# SUBBOARD-boost_filter_3p_LCL.net
KiCad netlist of a schematic drawn in Altium Designer
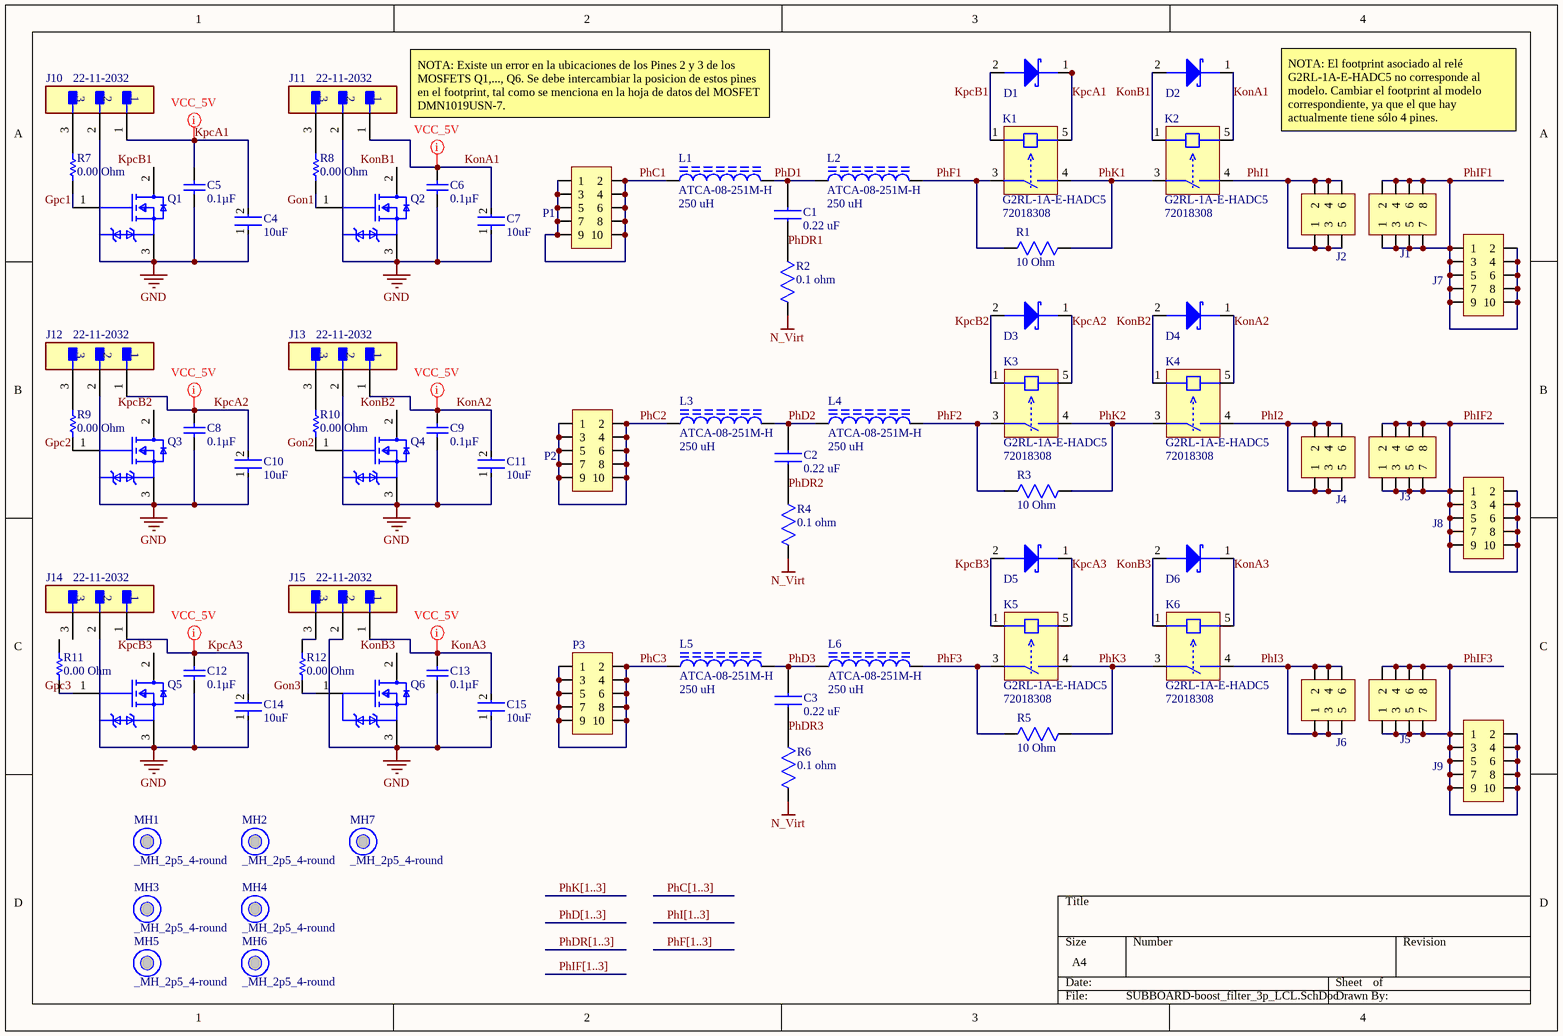
[diagram p0: SUBBOARD-boost_filter_3p_LCL.SchDoc]

(export (version "E")
  (design (tool "Eeschema 10.0.6"))
  (components
    (comp (ref "C1")
      (value "B32652A6224K")
      (footprint "B32652XXXXX")
      (description "Film Capacitors 0.22uF 630volts 5%")
      (fields
        (field (name "CAPACITANCE") "0.22 uF")
        (field (name "COPYRIGHT") "Copyright (C) 2018 Accelerated Designs. All rights reserved")
      )
      (libsource (lib "Altium_Library_POWERLAB") (part "B32652A6224K"))
    )
    (comp (ref "C2")
      (value "B32652A6224K")
      (footprint "B32652XXXXX")
      (description "Film Capacitors 0.22uF 630volts 5%")
      (fields
        (field (name "CAPACITANCE") "0.22 uF")
        (field (name "COPYRIGHT") "Copyright (C) 2018 Accelerated Designs. All rights reserved")
      )
      (libsource (lib "Altium_Library_POWERLAB") (part "B32652A6224K"))
    )
    (comp (ref "C3")
      (value "B32652A6224K")
      (footprint "B32652XXXXX")
      (description "Film Capacitors 0.22uF 630volts 5%")
      (fields
        (field (name "CAPACITANCE") "0.22 uF")
        (field (name "COPYRIGHT") "Copyright (C) 2018 Accelerated Designs. All rights reserved")
      )
      (libsource (lib "Altium_Library_POWERLAB") (part "B32652A6224K"))
    )
    (comp (ref "C4")
      (value "10uF")
      (footprint "FP-GRT31-0_2-MFG")
      (description "CAP CER 10UF 50V X5R 1206")
      (fields
        (field (name "TOLERANCE") "10%")
        (field (name "OCTOPART") "https://octopart.com/grt31cr61h106ke01l-murata-62921736")
      )
      (libsource (lib "Altium Content Vault") (part "11868f565c42a9108669ba33697ecf6"))
    )
    (comp (ref "C5")
      (value "CL10B104KB8NNNC")
      (footprint "SAMS-C0603-2_L")
      (description "Multi-layer Ceramic Capacitor, -55 to 125 degC, 2-Pin SMD (0603), RoHS, Tape and Reel")
      (fields (field (name "CAPACITANCE") "0.1µF") (field (name "MANUFACTURER") "Samsung Electro-Mechanics"))
      (libsource (lib "Altium Content Vault") (part "CAP-NP-2"))
    )
    (comp (ref "C6")
      (value "CL10B104KB8NNNC")
      (footprint "SAMS-C0603-2_L")
      (description "Multi-layer Ceramic Capacitor, -55 to 125 degC, 2-Pin SMD (0603), RoHS, Tape and Reel")
      (fields (field (name "CAPACITANCE") "0.1µF") (field (name "MANUFACTURER") "Samsung Electro-Mechanics"))
      (libsource (lib "Altium Content Vault") (part "CAP-NP-2"))
    )
    (comp (ref "C7")
      (value "10uF")
      (footprint "FP-GRT31-0_2-MFG")
      (description "CAP CER 10UF 50V X5R 1206")
      (fields
        (field (name "TOLERANCE") "10%")
        (field (name "OCTOPART") "https://octopart.com/grt31cr61h106ke01l-murata-62921736")
      )
      (libsource (lib "Altium Content Vault") (part "11868f565c42a9108669ba33697ecf6"))
    )
    (comp (ref "C8")
      (value "CL10B104KB8NNNC")
      (footprint "SAMS-C0603-2_L")
      (description "Multi-layer Ceramic Capacitor, -55 to 125 degC, 2-Pin SMD (0603), RoHS, Tape and Reel")
      (fields (field (name "CAPACITANCE") "0.1µF") (field (name "MANUFACTURER") "Samsung Electro-Mechanics"))
      (libsource (lib "Altium Content Vault") (part "CAP-NP-2"))
    )
    (comp (ref "C9")
      (value "CL10B104KB8NNNC")
      (footprint "SAMS-C0603-2_L")
      (description "Multi-layer Ceramic Capacitor, -55 to 125 degC, 2-Pin SMD (0603), RoHS, Tape and Reel")
      (fields (field (name "CAPACITANCE") "0.1µF") (field (name "MANUFACTURER") "Samsung Electro-Mechanics"))
      (libsource (lib "Altium Content Vault") (part "CAP-NP-2"))
    )
    (comp (ref "C10")
      (value "10uF")
      (footprint "FP-GRT31-0_2-MFG")
      (description "CAP CER 10UF 50V X5R 1206")
      (fields
        (field (name "TOLERANCE") "10%")
        (field (name "OCTOPART") "https://octopart.com/grt31cr61h106ke01l-murata-62921736")
      )
      (libsource (lib "Altium Content Vault") (part "11868f565c42a9108669ba33697ecf6"))
    )
    (comp (ref "C11")
      (value "10uF")
      (footprint "FP-GRT31-0_2-MFG")
      (description "CAP CER 10UF 50V X5R 1206")
      (fields
        (field (name "TOLERANCE") "10%")
        (field (name "OCTOPART") "https://octopart.com/grt31cr61h106ke01l-murata-62921736")
      )
      (libsource (lib "Altium Content Vault") (part "11868f565c42a9108669ba33697ecf6"))
    )
    (comp (ref "C12")
      (value "CL10B104KB8NNNC")
      (footprint "SAMS-C0603-2_L")
      (description "Multi-layer Ceramic Capacitor, -55 to 125 degC, 2-Pin SMD (0603), RoHS, Tape and Reel")
      (fields (field (name "CAPACITANCE") "0.1µF") (field (name "MANUFACTURER") "Samsung Electro-Mechanics"))
      (libsource (lib "Altium Content Vault") (part "CAP-NP-2"))
    )
    (comp (ref "C13")
      (value "CL10B104KB8NNNC")
      (footprint "SAMS-C0603-2_L")
      (description "Multi-layer Ceramic Capacitor, -55 to 125 degC, 2-Pin SMD (0603), RoHS, Tape and Reel")
      (fields (field (name "CAPACITANCE") "0.1µF") (field (name "MANUFACTURER") "Samsung Electro-Mechanics"))
      (libsource (lib "Altium Content Vault") (part "CAP-NP-2"))
    )
    (comp (ref "C14")
      (value "10uF")
      (footprint "FP-GRT31-0_2-MFG")
      (description "CAP CER 10UF 50V X5R 1206")
      (fields
        (field (name "TOLERANCE") "10%")
        (field (name "OCTOPART") "https://octopart.com/grt31cr61h106ke01l-murata-62921736")
      )
      (libsource (lib "Altium Content Vault") (part "11868f565c42a9108669ba33697ecf6"))
    )
    (comp (ref "C15")
      (value "10uF")
      (footprint "FP-GRT31-0_2-MFG")
      (description "CAP CER 10UF 50V X5R 1206")
      (fields
        (field (name "TOLERANCE") "10%")
        (field (name "OCTOPART") "https://octopart.com/grt31cr61h106ke01l-murata-62921736")
      )
      (libsource (lib "Altium Content Vault") (part "11868f565c42a9108669ba33697ecf6"))
    )
    (comp (ref "D1")
      (value "BYG23T-M3/TR")
      (footprint "BYG23T-M3/TR")
      (description "DIODE AVALANCHE 1300V 1A DO214AC")
      (fields (field (name "MANUFACTURER") "Vishay Semiconductors"))
      (libsource (lib "Altium_Library_POWERLAB") (part "BYG23T-M3/TR"))
    )
    (comp (ref "D2")
      (value "BYG23T-M3/TR")
      (footprint "BYG23T-M3/TR")
      (description "DIODE AVALANCHE 1300V 1A DO214AC")
      (fields (field (name "MANUFACTURER") "Vishay Semiconductors"))
      (libsource (lib "Altium_Library_POWERLAB") (part "BYG23T-M3/TR"))
    )
    (comp (ref "D3")
      (value "BYG23T-M3/TR")
      (footprint "BYG23T-M3/TR")
      (description "DIODE AVALANCHE 1300V 1A DO214AC")
      (fields (field (name "MANUFACTURER") "Vishay Semiconductors"))
      (libsource (lib "Altium_Library_POWERLAB") (part "BYG23T-M3/TR"))
    )
    (comp (ref "D4")
      (value "BYG23T-M3/TR")
      (footprint "BYG23T-M3/TR")
      (description "DIODE AVALANCHE 1300V 1A DO214AC")
      (fields (field (name "MANUFACTURER") "Vishay Semiconductors"))
      (libsource (lib "Altium_Library_POWERLAB") (part "BYG23T-M3/TR"))
    )
    (comp (ref "D5")
      (value "BYG23T-M3/TR")
      (footprint "BYG23T-M3/TR")
      (description "DIODE AVALANCHE 1300V 1A DO214AC")
      (fields (field (name "MANUFACTURER") "Vishay Semiconductors"))
      (libsource (lib "Altium_Library_POWERLAB") (part "BYG23T-M3/TR"))
    )
    (comp (ref "D6")
      (value "BYG23T-M3/TR")
      (footprint "BYG23T-M3/TR")
      (description "DIODE AVALANCHE 1300V 1A DO214AC")
      (fields (field (name "MANUFACTURER") "Vishay Semiconductors"))
      (libsource (lib "Altium_Library_POWERLAB") (part "BYG23T-M3/TR"))
    )
    (comp (ref "J1")
      (value "SSW-104-01-G-D")
      (footprint "SSW-104-01-G-D")
      (description "Conn Socket Strip SKT 8 POS 2.54mm Solder ST Thru-Hole")
      (fields (field (name "MANUFACTURER") "Samtec"))
      (libsource (lib "Altium_Library_POWERLAB") (part "SSW-104-01-G-D"))
    )
    (comp (ref "J2")
      (value "SSW-103-01-G-D")
      (footprint "SSW-103-01-G-D")
      (description "Conn Socket Strip SKT 6 POS 2.54mm Solder ST Thru-Hole")
      (fields (field (name "MANUFACTURER") "Samtec"))
      (libsource (lib "Altium_Library_POWERLAB") (part "SSW-103-01-G-D"))
    )
    (comp (ref "J3")
      (value "SSW-104-01-G-D")
      (footprint "SSW-104-01-G-D")
      (description "Conn Socket Strip SKT 8 POS 2.54mm Solder ST Thru-Hole")
      (fields (field (name "MANUFACTURER") "Samtec"))
      (libsource (lib "Altium_Library_POWERLAB") (part "SSW-104-01-G-D"))
    )
    (comp (ref "J4")
      (value "SSW-103-01-G-D")
      (footprint "SSW-103-01-G-D")
      (description "Conn Socket Strip SKT 6 POS 2.54mm Solder ST Thru-Hole")
      (fields (field (name "MANUFACTURER") "Samtec"))
      (libsource (lib "Altium_Library_POWERLAB") (part "SSW-103-01-G-D"))
    )
    (comp (ref "J5")
      (value "SSW-104-01-G-D")
      (footprint "SSW-104-01-G-D")
      (description "Conn Socket Strip SKT 8 POS 2.54mm Solder ST Thru-Hole")
      (fields (field (name "MANUFACTURER") "Samtec"))
      (libsource (lib "Altium_Library_POWERLAB") (part "SSW-104-01-G-D"))
    )
    (comp (ref "J6")
      (value "SSW-103-01-G-D")
      (footprint "SSW-103-01-G-D")
      (description "Conn Socket Strip SKT 6 POS 2.54mm Solder ST Thru-Hole")
      (fields (field (name "MANUFACTURER") "Samtec"))
      (libsource (lib "Altium_Library_POWERLAB") (part "SSW-103-01-G-D"))
    )
    (comp (ref "J7")
      (value "IPS1-105-01-L-D-RA")
      (footprint "IPS1-105-01-L-D-RA")
      (fields (field (name "MANUFACTURER") "Samtec"))
      (libsource (lib "Altium_Library_POWERLAB") (part "IPS1-105-01-L-D-RA"))
    )
    (comp (ref "J8")
      (value "IPS1-105-01-L-D-RA")
      (footprint "IPS1-105-01-L-D-RA")
      (fields (field (name "MANUFACTURER") "Samtec"))
      (libsource (lib "Altium_Library_POWERLAB") (part "IPS1-105-01-L-D-RA"))
    )
    (comp (ref "J9")
      (value "IPS1-105-01-L-D-RA")
      (footprint "IPS1-105-01-L-D-RA")
      (fields (field (name "MANUFACTURER") "Samtec"))
      (libsource (lib "Altium_Library_POWERLAB") (part "IPS1-105-01-L-D-RA"))
    )
    (comp (ref "J10")
      (value "22-11-2032")
      (footprint "FP-22-11-2032-MFG")
      (description "CONN HEADER VERT 3POS 2.54MM")
      (fields
        (field (name "MANUFACTURER") "Molex")
        (field (name "OCTOPART") "https://octopart.com/22-11-2032-molex-10085")
      )
      (libsource (lib "Altium Content Vault") (part "0d3f023dd272f625e17a2be33dea85f"))
    )
    (comp (ref "J11")
      (value "22-11-2032")
      (footprint "FP-22-11-2032-MFG")
      (description "CONN HEADER VERT 3POS 2.54MM")
      (fields
        (field (name "MANUFACTURER") "Molex")
        (field (name "OCTOPART") "https://octopart.com/22-11-2032-molex-10085")
      )
      (libsource (lib "Altium Content Vault") (part "0d3f023dd272f625e17a2be33dea85f"))
    )
    (comp (ref "J12")
      (value "22-11-2032")
      (footprint "FP-22-11-2032-MFG")
      (description "CONN HEADER VERT 3POS 2.54MM")
      (fields
        (field (name "MANUFACTURER") "Molex")
        (field (name "OCTOPART") "https://octopart.com/22-11-2032-molex-10085")
      )
      (libsource (lib "Altium Content Vault") (part "0d3f023dd272f625e17a2be33dea85f"))
    )
    (comp (ref "J13")
      (value "22-11-2032")
      (footprint "FP-22-11-2032-MFG")
      (description "CONN HEADER VERT 3POS 2.54MM")
      (fields
        (field (name "MANUFACTURER") "Molex")
        (field (name "OCTOPART") "https://octopart.com/22-11-2032-molex-10085")
      )
      (libsource (lib "Altium Content Vault") (part "0d3f023dd272f625e17a2be33dea85f"))
    )
    (comp (ref "J14")
      (value "22-11-2032")
      (footprint "FP-22-11-2032-MFG")
      (description "CONN HEADER VERT 3POS 2.54MM")
      (fields
        (field (name "MANUFACTURER") "Molex")
        (field (name "OCTOPART") "https://octopart.com/22-11-2032-molex-10085")
      )
      (libsource (lib "Altium Content Vault") (part "0d3f023dd272f625e17a2be33dea85f"))
    )
    (comp (ref "J15")
      (value "22-11-2032")
      (footprint "FP-22-11-2032-MFG")
      (description "CONN HEADER VERT 3POS 2.54MM")
      (fields
        (field (name "MANUFACTURER") "Molex")
        (field (name "OCTOPART") "https://octopart.com/22-11-2032-molex-10085")
      )
      (libsource (lib "Altium Content Vault") (part "0d3f023dd272f625e17a2be33dea85f"))
    )
    (comp (ref "K1")
      (value "G2RL-1A-E-HADC5")
      (footprint "G2RL-1A-E-HA DC5")
      (description "General Purpose Relays PCB Power Relay Low Profile 16A SPST-NO 5V coil voltage")
      (fields (field (name "MANUFACTURER") "Omron") (field (name "SUPPLIER PART NUMBER 1") "72018308"))
      (libsource (lib "Altium_Library_POWERLAB") (part "G2RL-1A-E-HADC5"))
    )
    (comp (ref "K2")
      (value "G2RL-1A-E-HADC5")
      (footprint "G2RL-1A-E-HA DC5")
      (description "General Purpose Relays PCB Power Relay Low Profile 16A SPST-NO 5V coil voltage")
      (fields (field (name "MANUFACTURER") "Omron") (field (name "SUPPLIER PART NUMBER 1") "72018308"))
      (libsource (lib "Altium_Library_POWERLAB") (part "G2RL-1A-E-HADC5"))
    )
    (comp (ref "K3")
      (value "G2RL-1A-E-HADC5")
      (footprint "G2RL-1A-E-HA DC5")
      (description "General Purpose Relays PCB Power Relay Low Profile 16A SPST-NO 5V coil voltage")
      (fields (field (name "MANUFACTURER") "Omron") (field (name "SUPPLIER PART NUMBER 1") "72018308"))
      (libsource (lib "Altium_Library_POWERLAB") (part "G2RL-1A-E-HADC5"))
    )
    (comp (ref "K4")
      (value "G2RL-1A-E-HADC5")
      (footprint "G2RL-1A-E-HA DC5")
      (description "General Purpose Relays PCB Power Relay Low Profile 16A SPST-NO 5V coil voltage")
      (fields (field (name "MANUFACTURER") "Omron") (field (name "SUPPLIER PART NUMBER 1") "72018308"))
      (libsource (lib "Altium_Library_POWERLAB") (part "G2RL-1A-E-HADC5"))
    )
    (comp (ref "K5")
      (value "G2RL-1A-E-HADC5")
      (footprint "G2RL-1A-E-HA DC5")
      (description "General Purpose Relays PCB Power Relay Low Profile 16A SPST-NO 5V coil voltage")
      (fields (field (name "MANUFACTURER") "Omron") (field (name "SUPPLIER PART NUMBER 1") "72018308"))
      (libsource (lib "Altium_Library_POWERLAB") (part "G2RL-1A-E-HADC5"))
    )
    (comp (ref "K6")
      (value "G2RL-1A-E-HADC5")
      (footprint "G2RL-1A-E-HA DC5")
      (description "General Purpose Relays PCB Power Relay Low Profile 16A SPST-NO 5V coil voltage")
      (fields (field (name "MANUFACTURER") "Omron") (field (name "SUPPLIER PART NUMBER 1") "72018308"))
      (libsource (lib "Altium_Library_POWERLAB") (part "G2RL-1A-E-HADC5"))
    )
    (comp (ref "L1")
      (value "ATCA-08-251M-H")
      (footprint "ATCA-08-251M-H")
      (description "Fixed Inductors 250uH 27 mOhm Max -40 C - 105 C - ABRACON")
      (fields (field (name "INDUCTANCE") "250 uH"))
      (libsource (lib "Altium_Library_POWERLAB") (part "ATCA-08-251M-H"))
    )
    (comp (ref "L2")
      (value "ATCA-08-251M-H")
      (footprint "ATCA-08-251M-H")
      (description "Fixed Inductors 250uH 27 mOhm Max -40 C - 105 C - ABRACON")
      (fields (field (name "INDUCTANCE") "250 uH"))
      (libsource (lib "Altium_Library_POWERLAB") (part "ATCA-08-251M-H"))
    )
    (comp (ref "L3")
      (value "ATCA-08-251M-H")
      (footprint "ATCA-08-251M-H")
      (description "Fixed Inductors 250uH 27 mOhm Max -40 C - 105 C - ABRACON")
      (fields (field (name "INDUCTANCE") "250 uH"))
      (libsource (lib "Altium_Library_POWERLAB") (part "ATCA-08-251M-H"))
    )
    (comp (ref "L4")
      (value "ATCA-08-251M-H")
      (footprint "ATCA-08-251M-H")
      (description "Fixed Inductors 250uH 27 mOhm Max -40 C - 105 C - ABRACON")
      (fields (field (name "INDUCTANCE") "250 uH"))
      (libsource (lib "Altium_Library_POWERLAB") (part "ATCA-08-251M-H"))
    )
    (comp (ref "L5")
      (value "ATCA-08-251M-H")
      (footprint "ATCA-08-251M-H")
      (description "Fixed Inductors 250uH 27 mOhm Max -40 C - 105 C - ABRACON")
      (fields (field (name "INDUCTANCE") "250 uH"))
      (libsource (lib "Altium_Library_POWERLAB") (part "ATCA-08-251M-H"))
    )
    (comp (ref "L6")
      (value "ATCA-08-251M-H")
      (footprint "ATCA-08-251M-H")
      (description "Fixed Inductors 250uH 27 mOhm Max -40 C - 105 C - ABRACON")
      (fields (field (name "INDUCTANCE") "250 uH"))
      (libsource (lib "Altium_Library_POWERLAB") (part "ATCA-08-251M-H"))
    )
    (comp (ref "MH1")
      (value "_MH_2p5_4-round")
      (footprint "_MH_2p5_4-round")
      (description "matching hole 2.5 hole, 4mm pad (round)")
      (libsource (lib "Altium_Library_POWERLAB") (part "_MH_2p5_4-round"))
    )
    (comp (ref "MH2")
      (value "_MH_2p5_4-round")
      (footprint "_MH_2p5_4-round")
      (description "matching hole 2.5 hole, 4mm pad (round)")
      (libsource (lib "Altium_Library_POWERLAB") (part "_MH_2p5_4-round"))
    )
    (comp (ref "MH3")
      (value "_MH_2p5_4-round")
      (footprint "_MH_2p5_4-round")
      (description "matching hole 2.5 hole, 4mm pad (round)")
      (libsource (lib "Altium_Library_POWERLAB") (part "_MH_2p5_4-round"))
    )
    (comp (ref "MH4")
      (value "_MH_2p5_4-round")
      (footprint "_MH_2p5_4-round")
      (description "matching hole 2.5 hole, 4mm pad (round)")
      (libsource (lib "Altium_Library_POWERLAB") (part "_MH_2p5_4-round"))
    )
    (comp (ref "MH5")
      (value "_MH_2p5_4-round")
      (footprint "_MH_2p5_4-round")
      (description "matching hole 2.5 hole, 4mm pad (round)")
      (libsource (lib "Altium_Library_POWERLAB") (part "_MH_2p5_4-round"))
    )
    (comp (ref "MH6")
      (value "_MH_2p5_4-round")
      (footprint "_MH_2p5_4-round")
      (description "matching hole 2.5 hole, 4mm pad (round)")
      (libsource (lib "Altium_Library_POWERLAB") (part "_MH_2p5_4-round"))
    )
    (comp (ref "MH7")
      (value "_MH_2p5_4-round")
      (footprint "_MH_2p5_4-round")
      (description "matching hole 2.5 hole, 4mm pad (round)")
      (libsource (lib "Altium_Library_POWERLAB") (part "_MH_2p5_4-round"))
    )
    (comp (ref "P1")
      (value "IPT1-105-01-S-D-RA")
      (footprint "IPT1-105-01-S-D-RA")
      (description "CONN PLUG .100\" 10POS DL PCB R/A")
      (fields (field (name "MANUFACTURER") "Samtec"))
      (libsource (lib "Altium_Library_POWERLAB") (part "IPT1-105-01-S-D-RA"))
    )
    (comp (ref "P2")
      (value "IPT1-105-01-S-D-RA")
      (footprint "IPT1-105-01-S-D-RA")
      (description "CONN PLUG .100\" 10POS DL PCB R/A")
      (fields (field (name "MANUFACTURER") "Samtec"))
      (libsource (lib "Altium_Library_POWERLAB") (part "IPT1-105-01-S-D-RA"))
    )
    (comp (ref "P3")
      (value "IPT1-105-01-S-D-RA")
      (footprint "IPT1-105-01-S-D-RA")
      (description "CONN PLUG .100\" 10POS DL PCB R/A")
      (fields (field (name "MANUFACTURER") "Samtec"))
      (libsource (lib "Altium_Library_POWERLAB") (part "IPT1-105-01-S-D-RA"))
    )
    (comp (ref "Q1")
      (value "DMN1019USN-7")
      (footprint "FP-SC59-IPC_B")
      (description "MOSFET N-CH 12V 9.3A SC59")
      (libsource (lib "Altium Content Vault") (part "587d6cfc489599008faafaa59ebe43c"))
    )
    (comp (ref "Q2")
      (value "DMN1019USN-7")
      (footprint "FP-SC59-IPC_B")
      (description "MOSFET N-CH 12V 9.3A SC59")
      (libsource (lib "Altium Content Vault") (part "587d6cfc489599008faafaa59ebe43c"))
    )
    (comp (ref "Q3")
      (value "DMN1019USN-7")
      (footprint "FP-SC59-IPC_B")
      (description "MOSFET N-CH 12V 9.3A SC59")
      (libsource (lib "Altium Content Vault") (part "587d6cfc489599008faafaa59ebe43c"))
    )
    (comp (ref "Q4")
      (value "DMN1019USN-7")
      (footprint "FP-SC59-IPC_B")
      (description "MOSFET N-CH 12V 9.3A SC59")
      (libsource (lib "Altium Content Vault") (part "587d6cfc489599008faafaa59ebe43c"))
    )
    (comp (ref "Q5")
      (value "DMN1019USN-7")
      (footprint "FP-SC59-IPC_B")
      (description "MOSFET N-CH 12V 9.3A SC59")
      (libsource (lib "Altium Content Vault") (part "587d6cfc489599008faafaa59ebe43c"))
    )
    (comp (ref "Q6")
      (value "DMN1019USN-7")
      (footprint "FP-SC59-IPC_B")
      (description "MOSFET N-CH 12V 9.3A SC59")
      (libsource (lib "Altium Content Vault") (part "587d6cfc489599008faafaa59ebe43c"))
    )
    (comp (ref "R1")
      (value "WHE10RFET")
      (footprint "RES_WH/NE")
      (description "Wirewound Resistors - Through Hole 5W 10 ohm 1%")
      (fields
        (field (name "TOLERANCE") "1%")
        (field (name "RESISTANCE") "10 Ohm")
        (field (name "COPYRIGHT") "Copyright (C) 2018 Accelerated Designs. All rights reserved")
      )
      (libsource (lib "Altium_Library_POWERLAB") (part "WHE10RFET"))
    )
    (comp (ref "R2")
      (value "WSR5R1000FEA")
      (footprint "WSR-L")
      (description "RES 0.1 OHM 1% 5W 4527")
      (fields
        (field (name "RESISTANCE") "0.1 ohm")
        (field (name "COPYRIGHT") "Copyright (C) 2018 Accelerated Designs. All rights reserved")
      )
      (libsource (lib "Altium_Library_POWERLAB") (part "WSR5R1000FEA"))
    )
    (comp (ref "R3")
      (value "WHE10RFET")
      (footprint "RES_WH/NE")
      (description "Wirewound Resistors - Through Hole 5W 10 ohm 1%")
      (fields
        (field (name "TOLERANCE") "1%")
        (field (name "RESISTANCE") "10 Ohm")
        (field (name "COPYRIGHT") "Copyright (C) 2018 Accelerated Designs. All rights reserved")
      )
      (libsource (lib "Altium_Library_POWERLAB") (part "WHE10RFET"))
    )
    (comp (ref "R4")
      (value "WSR5R1000FEA")
      (footprint "WSR-L")
      (description "RES 0.1 OHM 1% 5W 4527")
      (fields
        (field (name "RESISTANCE") "0.1 ohm")
        (field (name "COPYRIGHT") "Copyright (C) 2018 Accelerated Designs. All rights reserved")
      )
      (libsource (lib "Altium_Library_POWERLAB") (part "WSR5R1000FEA"))
    )
    (comp (ref "R5")
      (value "WHE10RFET")
      (footprint "RES_WH/NE")
      (description "Wirewound Resistors - Through Hole 5W 10 ohm 1%")
      (fields
        (field (name "TOLERANCE") "1%")
        (field (name "RESISTANCE") "10 Ohm")
        (field (name "COPYRIGHT") "Copyright (C) 2018 Accelerated Designs. All rights reserved")
      )
      (libsource (lib "Altium_Library_POWERLAB") (part "WHE10RFET"))
    )
    (comp (ref "R6")
      (value "WSR5R1000FEA")
      (footprint "WSR-L")
      (description "RES 0.1 OHM 1% 5W 4527")
      (fields
        (field (name "RESISTANCE") "0.1 ohm")
        (field (name "COPYRIGHT") "Copyright (C) 2018 Accelerated Designs. All rights reserved")
      )
      (libsource (lib "Altium_Library_POWERLAB") (part "WSR5R1000FEA"))
    )
    (comp (ref "R7")
      (value "0.00 Ohm")
      (footprint "RESC0603(1608)_L")
      (description "Jumper 0603 (1608 Metric)")
      (fields (field (name "POWER") "None") (field (name "Comment") "Jumper 0603(1608)"))
      (libsource (lib "Altium Content Vault") (part "RES"))
    )
    (comp (ref "R8")
      (value "0.00 Ohm")
      (footprint "RESC0603(1608)_L")
      (description "Jumper 0603 (1608 Metric)")
      (fields (field (name "POWER") "None") (field (name "Comment") "Jumper 0603(1608)"))
      (libsource (lib "Altium Content Vault") (part "RES"))
    )
    (comp (ref "R9")
      (value "0.00 Ohm")
      (footprint "RESC0603(1608)_L")
      (description "Jumper 0603 (1608 Metric)")
      (fields (field (name "POWER") "None") (field (name "Comment") "Jumper 0603(1608)"))
      (libsource (lib "Altium Content Vault") (part "RES"))
    )
    (comp (ref "R10")
      (value "0.00 Ohm")
      (footprint "RESC0603(1608)_L")
      (description "Jumper 0603 (1608 Metric)")
      (fields (field (name "POWER") "None") (field (name "Comment") "Jumper 0603(1608)"))
      (libsource (lib "Altium Content Vault") (part "RES"))
    )
    (comp (ref "R11")
      (value "0.00 Ohm")
      (footprint "RESC0603(1608)_L")
      (description "Jumper 0603 (1608 Metric)")
      (fields (field (name "POWER") "None") (field (name "Comment") "Jumper 0603(1608)"))
      (libsource (lib "Altium Content Vault") (part "RES"))
    )
    (comp (ref "R12")
      (value "0.00 Ohm")
      (footprint "RESC0603(1608)_L")
      (description "Jumper 0603 (1608 Metric)")
      (fields (field (name "POWER") "None") (field (name "Comment") "Jumper 0603(1608)"))
      (libsource (lib "Altium Content Vault") (part "RES"))
    )
  )
  (nets
    (net (code "1") (name "/Gon1") (class "Default")
      (node (ref "Q2") (pin "1") (pinfunction "G_1") (pintype "passive"))
      (node (ref "R8") (pin "2") (pinfunction "2_2") (pintype "passive"))
    )
    (net (code "2") (name "/Gon2") (class "Default")
      (node (ref "Q4") (pin "1") (pinfunction "G_1") (pintype "passive"))
      (node (ref "R10") (pin "2") (pinfunction "2_2") (pintype "passive"))
    )
    (net (code "3") (name "/Gon3") (class "Default")
      (node (ref "Q6") (pin "1") (pinfunction "G_1") (pintype "passive"))
      (node (ref "R12") (pin "2") (pinfunction "2_2") (pintype "passive"))
    )
    (net (code "4") (name "/Gpc1") (class "Default")
      (node (ref "Q1") (pin "1") (pinfunction "G_1") (pintype "passive"))
      (node (ref "R7") (pin "2") (pinfunction "2_2") (pintype "passive"))
    )
    (net (code "5") (name "/Gpc2") (class "Default")
      (node (ref "Q3") (pin "1") (pinfunction "G_1") (pintype "passive"))
      (node (ref "R9") (pin "2") (pinfunction "2_2") (pintype "passive"))
    )
    (net (code "6") (name "/Gpc3") (class "Default")
      (node (ref "Q5") (pin "1") (pinfunction "G_1") (pintype "passive"))
      (node (ref "R11") (pin "2") (pinfunction "2_2") (pintype "passive"))
    )
    (net (code "7") (name "/KonA1") (class "Default")
      (node (ref "C6") (pin "1") (pinfunction "1_1") (pintype "passive"))
      (node (ref "C7") (pin "2") (pinfunction "2_2") (pintype "passive"))
      (node (ref "D2") (pin "1") (pinfunction "Cathode_1") (pintype "passive"))
      (node (ref "J11") (pin "1") (pinfunction "1_1") (pintype "passive"))
      (node (ref "K2") (pin "5") (pinfunction "5_5") (pintype "passive"))
    )
    (net (code "8") (name "/KonA2") (class "Default")
      (node (ref "C11") (pin "2") (pinfunction "2_2") (pintype "passive"))
      (node (ref "C9") (pin "1") (pinfunction "1_1") (pintype "passive"))
      (node (ref "D4") (pin "1") (pinfunction "Cathode_1") (pintype "passive"))
      (node (ref "J13") (pin "1") (pinfunction "1_1") (pintype "passive"))
      (node (ref "K4") (pin "5") (pinfunction "5_5") (pintype "passive"))
    )
    (net (code "9") (name "/KonA3") (class "Default")
      (node (ref "C13") (pin "1") (pinfunction "1_1") (pintype "passive"))
      (node (ref "C15") (pin "2") (pinfunction "2_2") (pintype "passive"))
      (node (ref "D6") (pin "1") (pinfunction "Cathode_1") (pintype "passive"))
      (node (ref "J15") (pin "1") (pinfunction "1_1") (pintype "passive"))
      (node (ref "K6") (pin "5") (pinfunction "5_5") (pintype "passive"))
    )
    (net (code "10") (name "/KonB1") (class "Default")
      (node (ref "D2") (pin "2") (pinfunction "Anode_2") (pintype "passive"))
      (node (ref "K2") (pin "1") (pinfunction "1_1") (pintype "passive"))
      (node (ref "Q2") (pin "2") (pinfunction "S_2") (pintype "passive"))
    )
    (net (code "11") (name "/KonB2") (class "Default")
      (node (ref "D4") (pin "2") (pinfunction "Anode_2") (pintype "passive"))
      (node (ref "K4") (pin "1") (pinfunction "1_1") (pintype "passive"))
      (node (ref "Q4") (pin "2") (pinfunction "S_2") (pintype "passive"))
    )
    (net (code "12") (name "/KonB3") (class "Default")
      (node (ref "D6") (pin "2") (pinfunction "Anode_2") (pintype "passive"))
      (node (ref "K6") (pin "1") (pinfunction "1_1") (pintype "passive"))
      (node (ref "Q6") (pin "2") (pinfunction "S_2") (pintype "passive"))
    )
    (net (code "13") (name "/KpcA1") (class "Default")
      (node (ref "C4") (pin "2") (pinfunction "2_2") (pintype "passive"))
      (node (ref "C5") (pin "1") (pinfunction "1_1") (pintype "passive"))
      (node (ref "D1") (pin "1") (pinfunction "Cathode_1") (pintype "passive"))
      (node (ref "J10") (pin "1") (pinfunction "1_1") (pintype "passive"))
      (node (ref "K1") (pin "5") (pinfunction "5_5") (pintype "passive"))
    )
    (net (code "14") (name "/KpcA2") (class "Default")
      (node (ref "C10") (pin "2") (pinfunction "2_2") (pintype "passive"))
      (node (ref "C8") (pin "1") (pinfunction "1_1") (pintype "passive"))
      (node (ref "D3") (pin "1") (pinfunction "Cathode_1") (pintype "passive"))
      (node (ref "J12") (pin "1") (pinfunction "1_1") (pintype "passive"))
      (node (ref "K3") (pin "5") (pinfunction "5_5") (pintype "passive"))
    )
    (net (code "15") (name "/KpcA3") (class "Default")
      (node (ref "C12") (pin "1") (pinfunction "1_1") (pintype "passive"))
      (node (ref "C14") (pin "2") (pinfunction "2_2") (pintype "passive"))
      (node (ref "D5") (pin "1") (pinfunction "Cathode_1") (pintype "passive"))
      (node (ref "J14") (pin "1") (pinfunction "1_1") (pintype "passive"))
      (node (ref "K5") (pin "5") (pinfunction "5_5") (pintype "passive"))
    )
    (net (code "16") (name "/KpcB1") (class "Default")
      (node (ref "D1") (pin "2") (pinfunction "Anode_2") (pintype "passive"))
      (node (ref "K1") (pin "1") (pinfunction "1_1") (pintype "passive"))
      (node (ref "Q1") (pin "2") (pinfunction "S_2") (pintype "passive"))
    )
    (net (code "17") (name "/KpcB2") (class "Default")
      (node (ref "D3") (pin "2") (pinfunction "Anode_2") (pintype "passive"))
      (node (ref "K3") (pin "1") (pinfunction "1_1") (pintype "passive"))
      (node (ref "Q3") (pin "2") (pinfunction "S_2") (pintype "passive"))
    )
    (net (code "18") (name "/KpcB3") (class "Default")
      (node (ref "D5") (pin "2") (pinfunction "Anode_2") (pintype "passive"))
      (node (ref "K5") (pin "1") (pinfunction "1_1") (pintype "passive"))
      (node (ref "Q5") (pin "2") (pinfunction "S_2") (pintype "passive"))
    )
    (net (code "19") (name "/PhC1") (class "Default")
      (node (ref "L1") (pin "1") (pinfunction "1_1") (pintype "passive"))
      (node (ref "P1") (pin "1") (pinfunction "1_1") (pintype "passive"))
      (node (ref "P1") (pin "10") (pinfunction "10_10") (pintype "passive"))
      (node (ref "P1") (pin "2") (pinfunction "2_2") (pintype "passive"))
      (node (ref "P1") (pin "3") (pinfunction "3_3") (pintype "passive"))
      (node (ref "P1") (pin "4") (pinfunction "4_4") (pintype "passive"))
      (node (ref "P1") (pin "5") (pinfunction "5_5") (pintype "passive"))
      (node (ref "P1") (pin "6") (pinfunction "6_6") (pintype "passive"))
      (node (ref "P1") (pin "7") (pinfunction "7_7") (pintype "passive"))
      (node (ref "P1") (pin "8") (pinfunction "8_8") (pintype "passive"))
      (node (ref "P1") (pin "9") (pinfunction "9_9") (pintype "passive"))
    )
    (net (code "20") (name "/PhC2") (class "Default")
      (node (ref "L3") (pin "1") (pinfunction "1_1") (pintype "passive"))
      (node (ref "P2") (pin "1") (pinfunction "1_1") (pintype "passive"))
      (node (ref "P2") (pin "10") (pinfunction "10_10") (pintype "passive"))
      (node (ref "P2") (pin "2") (pinfunction "2_2") (pintype "passive"))
      (node (ref "P2") (pin "3") (pinfunction "3_3") (pintype "passive"))
      (node (ref "P2") (pin "4") (pinfunction "4_4") (pintype "passive"))
      (node (ref "P2") (pin "5") (pinfunction "5_5") (pintype "passive"))
      (node (ref "P2") (pin "6") (pinfunction "6_6") (pintype "passive"))
      (node (ref "P2") (pin "7") (pinfunction "7_7") (pintype "passive"))
      (node (ref "P2") (pin "8") (pinfunction "8_8") (pintype "passive"))
      (node (ref "P2") (pin "9") (pinfunction "9_9") (pintype "passive"))
    )
    (net (code "21") (name "/PhC3") (class "Default")
      (node (ref "L5") (pin "1") (pinfunction "1_1") (pintype "passive"))
      (node (ref "P3") (pin "1") (pinfunction "1_1") (pintype "passive"))
      (node (ref "P3") (pin "10") (pinfunction "10_10") (pintype "passive"))
      (node (ref "P3") (pin "2") (pinfunction "2_2") (pintype "passive"))
      (node (ref "P3") (pin "3") (pinfunction "3_3") (pintype "passive"))
      (node (ref "P3") (pin "4") (pinfunction "4_4") (pintype "passive"))
      (node (ref "P3") (pin "5") (pinfunction "5_5") (pintype "passive"))
      (node (ref "P3") (pin "6") (pinfunction "6_6") (pintype "passive"))
      (node (ref "P3") (pin "7") (pinfunction "7_7") (pintype "passive"))
      (node (ref "P3") (pin "8") (pinfunction "8_8") (pintype "passive"))
      (node (ref "P3") (pin "9") (pinfunction "9_9") (pintype "passive"))
    )
    (net (code "23") (name "/PhD1") (class "Default")
      (node (ref "C1") (pin "2") (pinfunction "2_2") (pintype "passive"))
      (node (ref "L1") (pin "2") (pinfunction "2_2") (pintype "passive"))
      (node (ref "L2") (pin "1") (pinfunction "1_1") (pintype "passive"))
    )
    (net (code "24") (name "/PhD2") (class "Default")
      (node (ref "C2") (pin "2") (pinfunction "2_2") (pintype "passive"))
      (node (ref "L3") (pin "2") (pinfunction "2_2") (pintype "passive"))
      (node (ref "L4") (pin "1") (pinfunction "1_1") (pintype "passive"))
    )
    (net (code "25") (name "/PhD3") (class "Default")
      (node (ref "C3") (pin "2") (pinfunction "2_2") (pintype "passive"))
      (node (ref "L5") (pin "2") (pinfunction "2_2") (pintype "passive"))
      (node (ref "L6") (pin "1") (pinfunction "1_1") (pintype "passive"))
    )
    (net (code "26") (name "/PhDR1") (class "Default")
      (node (ref "C1") (pin "1") (pinfunction "1_1") (pintype "passive"))
      (node (ref "R2") (pin "2") (pinfunction "2_2") (pintype "passive"))
    )
    (net (code "27") (name "/PhDR2") (class "Default")
      (node (ref "C2") (pin "1") (pinfunction "1_1") (pintype "passive"))
      (node (ref "R4") (pin "2") (pinfunction "2_2") (pintype "passive"))
    )
    (net (code "28") (name "/PhDR3") (class "Default")
      (node (ref "C3") (pin "1") (pinfunction "1_1") (pintype "passive"))
      (node (ref "R6") (pin "2") (pinfunction "2_2") (pintype "passive"))
    )
    (net (code "31") (name "/PhF1") (class "Default")
      (node (ref "K1") (pin "3") (pinfunction "3_3") (pintype "passive"))
      (node (ref "L2") (pin "2") (pinfunction "2_2") (pintype "passive"))
      (node (ref "R1") (pin "1") (pinfunction "1_1") (pintype "passive"))
    )
    (net (code "32") (name "/PhF2") (class "Default")
      (node (ref "K3") (pin "3") (pinfunction "3_3") (pintype "passive"))
      (node (ref "L4") (pin "2") (pinfunction "2_2") (pintype "passive"))
      (node (ref "R3") (pin "1") (pinfunction "1_1") (pintype "passive"))
    )
    (net (code "33") (name "/PhF3") (class "Default")
      (node (ref "K5") (pin "3") (pinfunction "3_3") (pintype "passive"))
      (node (ref "L6") (pin "2") (pinfunction "2_2") (pintype "passive"))
      (node (ref "R5") (pin "1") (pinfunction "1_1") (pintype "passive"))
    )
    (net (code "35") (name "/PhI1") (class "Default")
      (node (ref "J2") (pin "1") (pinfunction "1_1") (pintype "passive"))
      (node (ref "J2") (pin "2") (pinfunction "2_2") (pintype "passive"))
      (node (ref "J2") (pin "3") (pinfunction "3_3") (pintype "passive"))
      (node (ref "J2") (pin "4") (pinfunction "4_4") (pintype "passive"))
      (node (ref "J2") (pin "5") (pinfunction "5_5") (pintype "passive"))
      (node (ref "J2") (pin "6") (pinfunction "6_6") (pintype "passive"))
      (node (ref "K2") (pin "4") (pinfunction "4_4") (pintype "passive"))
    )
    (net (code "36") (name "/PhI2") (class "Default")
      (node (ref "J4") (pin "1") (pinfunction "1_1") (pintype "passive"))
      (node (ref "J4") (pin "2") (pinfunction "2_2") (pintype "passive"))
      (node (ref "J4") (pin "3") (pinfunction "3_3") (pintype "passive"))
      (node (ref "J4") (pin "4") (pinfunction "4_4") (pintype "passive"))
      (node (ref "J4") (pin "5") (pinfunction "5_5") (pintype "passive"))
      (node (ref "J4") (pin "6") (pinfunction "6_6") (pintype "passive"))
      (node (ref "K4") (pin "4") (pinfunction "4_4") (pintype "passive"))
    )
    (net (code "37") (name "/PhI3") (class "Default")
      (node (ref "J6") (pin "1") (pinfunction "1_1") (pintype "passive"))
      (node (ref "J6") (pin "2") (pinfunction "2_2") (pintype "passive"))
      (node (ref "J6") (pin "3") (pinfunction "3_3") (pintype "passive"))
      (node (ref "J6") (pin "4") (pinfunction "4_4") (pintype "passive"))
      (node (ref "J6") (pin "5") (pinfunction "5_5") (pintype "passive"))
      (node (ref "J6") (pin "6") (pinfunction "6_6") (pintype "passive"))
      (node (ref "K6") (pin "4") (pinfunction "4_4") (pintype "passive"))
    )
    (net (code "38") (name "/PhIF1") (class "Default")
      (node (ref "J1") (pin "1") (pinfunction "1_1") (pintype "passive"))
      (node (ref "J1") (pin "2") (pinfunction "2_2") (pintype "passive"))
      (node (ref "J1") (pin "3") (pinfunction "3_3") (pintype "passive"))
      (node (ref "J1") (pin "4") (pinfunction "4_4") (pintype "passive"))
      (node (ref "J1") (pin "5") (pinfunction "5_5") (pintype "passive"))
      (node (ref "J1") (pin "6") (pinfunction "6_6") (pintype "passive"))
      (node (ref "J1") (pin "7") (pinfunction "7_7") (pintype "passive"))
      (node (ref "J1") (pin "8") (pinfunction "8_8") (pintype "passive"))
      (node (ref "J7") (pin "1") (pinfunction "1_1") (pintype "passive"))
      (node (ref "J7") (pin "10") (pinfunction "10_10") (pintype "passive"))
      (node (ref "J7") (pin "2") (pinfunction "2_2") (pintype "passive"))
      (node (ref "J7") (pin "3") (pinfunction "3_3") (pintype "passive"))
      (node (ref "J7") (pin "4") (pinfunction "4_4") (pintype "passive"))
      (node (ref "J7") (pin "5") (pinfunction "5_5") (pintype "passive"))
      (node (ref "J7") (pin "6") (pinfunction "6_6") (pintype "passive"))
      (node (ref "J7") (pin "7") (pinfunction "7_7") (pintype "passive"))
      (node (ref "J7") (pin "8") (pinfunction "8_8") (pintype "passive"))
      (node (ref "J7") (pin "9") (pinfunction "9_9") (pintype "passive"))
    )
    (net (code "39") (name "/PhIF2") (class "Default")
      (node (ref "J3") (pin "1") (pinfunction "1_1") (pintype "passive"))
      (node (ref "J3") (pin "2") (pinfunction "2_2") (pintype "passive"))
      (node (ref "J3") (pin "3") (pinfunction "3_3") (pintype "passive"))
      (node (ref "J3") (pin "4") (pinfunction "4_4") (pintype "passive"))
      (node (ref "J3") (pin "5") (pinfunction "5_5") (pintype "passive"))
      (node (ref "J3") (pin "6") (pinfunction "6_6") (pintype "passive"))
      (node (ref "J3") (pin "7") (pinfunction "7_7") (pintype "passive"))
      (node (ref "J3") (pin "8") (pinfunction "8_8") (pintype "passive"))
      (node (ref "J8") (pin "1") (pinfunction "1_1") (pintype "passive"))
      (node (ref "J8") (pin "10") (pinfunction "10_10") (pintype "passive"))
      (node (ref "J8") (pin "2") (pinfunction "2_2") (pintype "passive"))
      (node (ref "J8") (pin "3") (pinfunction "3_3") (pintype "passive"))
      (node (ref "J8") (pin "4") (pinfunction "4_4") (pintype "passive"))
      (node (ref "J8") (pin "5") (pinfunction "5_5") (pintype "passive"))
      (node (ref "J8") (pin "6") (pinfunction "6_6") (pintype "passive"))
      (node (ref "J8") (pin "7") (pinfunction "7_7") (pintype "passive"))
      (node (ref "J8") (pin "8") (pinfunction "8_8") (pintype "passive"))
      (node (ref "J8") (pin "9") (pinfunction "9_9") (pintype "passive"))
    )
    (net (code "40") (name "/PhIF3") (class "Default")
      (node (ref "J5") (pin "1") (pinfunction "1_1") (pintype "passive"))
      (node (ref "J5") (pin "2") (pinfunction "2_2") (pintype "passive"))
      (node (ref "J5") (pin "3") (pinfunction "3_3") (pintype "passive"))
      (node (ref "J5") (pin "4") (pinfunction "4_4") (pintype "passive"))
      (node (ref "J5") (pin "5") (pinfunction "5_5") (pintype "passive"))
      (node (ref "J5") (pin "6") (pinfunction "6_6") (pintype "passive"))
      (node (ref "J5") (pin "7") (pinfunction "7_7") (pintype "passive"))
      (node (ref "J5") (pin "8") (pinfunction "8_8") (pintype "passive"))
      (node (ref "J9") (pin "1") (pinfunction "1_1") (pintype "passive"))
      (node (ref "J9") (pin "10") (pinfunction "10_10") (pintype "passive"))
      (node (ref "J9") (pin "2") (pinfunction "2_2") (pintype "passive"))
      (node (ref "J9") (pin "3") (pinfunction "3_3") (pintype "passive"))
      (node (ref "J9") (pin "4") (pinfunction "4_4") (pintype "passive"))
      (node (ref "J9") (pin "5") (pinfunction "5_5") (pintype "passive"))
      (node (ref "J9") (pin "6") (pinfunction "6_6") (pintype "passive"))
      (node (ref "J9") (pin "7") (pinfunction "7_7") (pintype "passive"))
      (node (ref "J9") (pin "8") (pinfunction "8_8") (pintype "passive"))
      (node (ref "J9") (pin "9") (pinfunction "9_9") (pintype "passive"))
    )
    (net (code "43") (name "/PhK1") (class "Default")
      (node (ref "K1") (pin "4") (pinfunction "4_4") (pintype "passive"))
      (node (ref "K2") (pin "3") (pinfunction "3_3") (pintype "passive"))
      (node (ref "R1") (pin "2") (pinfunction "2_2") (pintype "passive"))
    )
    (net (code "44") (name "/PhK2") (class "Default")
      (node (ref "K3") (pin "4") (pinfunction "4_4") (pintype "passive"))
      (node (ref "K4") (pin "3") (pinfunction "3_3") (pintype "passive"))
      (node (ref "R3") (pin "2") (pinfunction "2_2") (pintype "passive"))
    )
    (net (code "45") (name "/PhK3") (class "Default")
      (node (ref "K5") (pin "4") (pinfunction "4_4") (pintype "passive"))
      (node (ref "K6") (pin "3") (pinfunction "3_3") (pintype "passive"))
      (node (ref "R5") (pin "2") (pinfunction "2_2") (pintype "passive"))
    )
    (net (code "47") (name "GND") (class "Default")
      (node (ref "C10") (pin "1") (pinfunction "1_1") (pintype "passive"))
      (node (ref "C11") (pin "1") (pinfunction "1_1") (pintype "passive"))
      (node (ref "C12") (pin "2") (pinfunction "2_2") (pintype "passive"))
      (node (ref "C13") (pin "2") (pinfunction "2_2") (pintype "passive"))
      (node (ref "C14") (pin "1") (pinfunction "1_1") (pintype "passive"))
      (node (ref "C15") (pin "1") (pinfunction "1_1") (pintype "passive"))
      (node (ref "C4") (pin "1") (pinfunction "1_1") (pintype "passive"))
      (node (ref "C5") (pin "2") (pinfunction "2_2") (pintype "passive"))
      (node (ref "C6") (pin "2") (pinfunction "2_2") (pintype "passive"))
      (node (ref "C7") (pin "1") (pinfunction "1_1") (pintype "passive"))
      (node (ref "C8") (pin "2") (pinfunction "2_2") (pintype "passive"))
      (node (ref "C9") (pin "2") (pinfunction "2_2") (pintype "passive"))
      (node (ref "J10") (pin "2") (pinfunction "2_2") (pintype "passive"))
      (node (ref "J11") (pin "2") (pinfunction "2_2") (pintype "passive"))
      (node (ref "J12") (pin "2") (pinfunction "2_2") (pintype "passive"))
      (node (ref "J13") (pin "2") (pinfunction "2_2") (pintype "passive"))
      (node (ref "J14") (pin "2") (pinfunction "2_2") (pintype "passive"))
      (node (ref "J15") (pin "2") (pinfunction "2_2") (pintype "passive"))
      (node (ref "Q1") (pin "3") (pinfunction "D_3") (pintype "passive"))
      (node (ref "Q2") (pin "3") (pinfunction "D_3") (pintype "passive"))
      (node (ref "Q3") (pin "3") (pinfunction "D_3") (pintype "passive"))
      (node (ref "Q4") (pin "3") (pinfunction "D_3") (pintype "passive"))
      (node (ref "Q5") (pin "3") (pinfunction "D_3") (pintype "passive"))
      (node (ref "Q6") (pin "3") (pinfunction "D_3") (pintype "passive"))
    )
    (net (code "48") (name "N_Virt") (class "Default")
      (node (ref "R2") (pin "1") (pinfunction "1_1") (pintype "passive"))
      (node (ref "R4") (pin "1") (pinfunction "1_1") (pintype "passive"))
      (node (ref "R6") (pin "1") (pinfunction "1_1") (pintype "passive"))
    )
    (net (code "49") (name "Net-(J10-Pad3)") (class "Default")
      (node (ref "J10") (pin "3") (pinfunction "3_3") (pintype "passive"))
      (node (ref "R7") (pin "1") (pinfunction "1_1") (pintype "passive"))
    )
    (net (code "50") (name "Net-(J11-Pad3)") (class "Default")
      (node (ref "J11") (pin "3") (pinfunction "3_3") (pintype "passive"))
      (node (ref "R8") (pin "1") (pinfunction "1_1") (pintype "passive"))
    )
    (net (code "51") (name "Net-(J12-Pad3)") (class "Default")
      (node (ref "J12") (pin "3") (pinfunction "3_3") (pintype "passive"))
      (node (ref "R9") (pin "1") (pinfunction "1_1") (pintype "passive"))
    )
    (net (code "52") (name "Net-(J13-Pad3)") (class "Default")
      (node (ref "J13") (pin "3") (pinfunction "3_3") (pintype "passive"))
      (node (ref "R10") (pin "1") (pinfunction "1_1") (pintype "passive"))
    )
    (net (code "53") (name "Net-(J15-Pad3)") (class "Default")
      (node (ref "J15") (pin "3") (pinfunction "3_3") (pintype "passive"))
      (node (ref "R12") (pin "1") (pinfunction "1_1") (pintype "passive"))
    )
    (net (code "54") (name "unconnected-(J14-Pad3)") (class "Default")
      (node (ref "J14") (pin "3") (pinfunction "3_3") (pintype "passive"))
    )
    (net (code "55") (name "unconnected-(R11-Pad1)") (class "Default")
      (node (ref "R11") (pin "1") (pinfunction "1_1") (pintype "passive"))
    )
  )
)
